# Motor2.net
KiCad netlist of a schematic drawn in Altium Designer
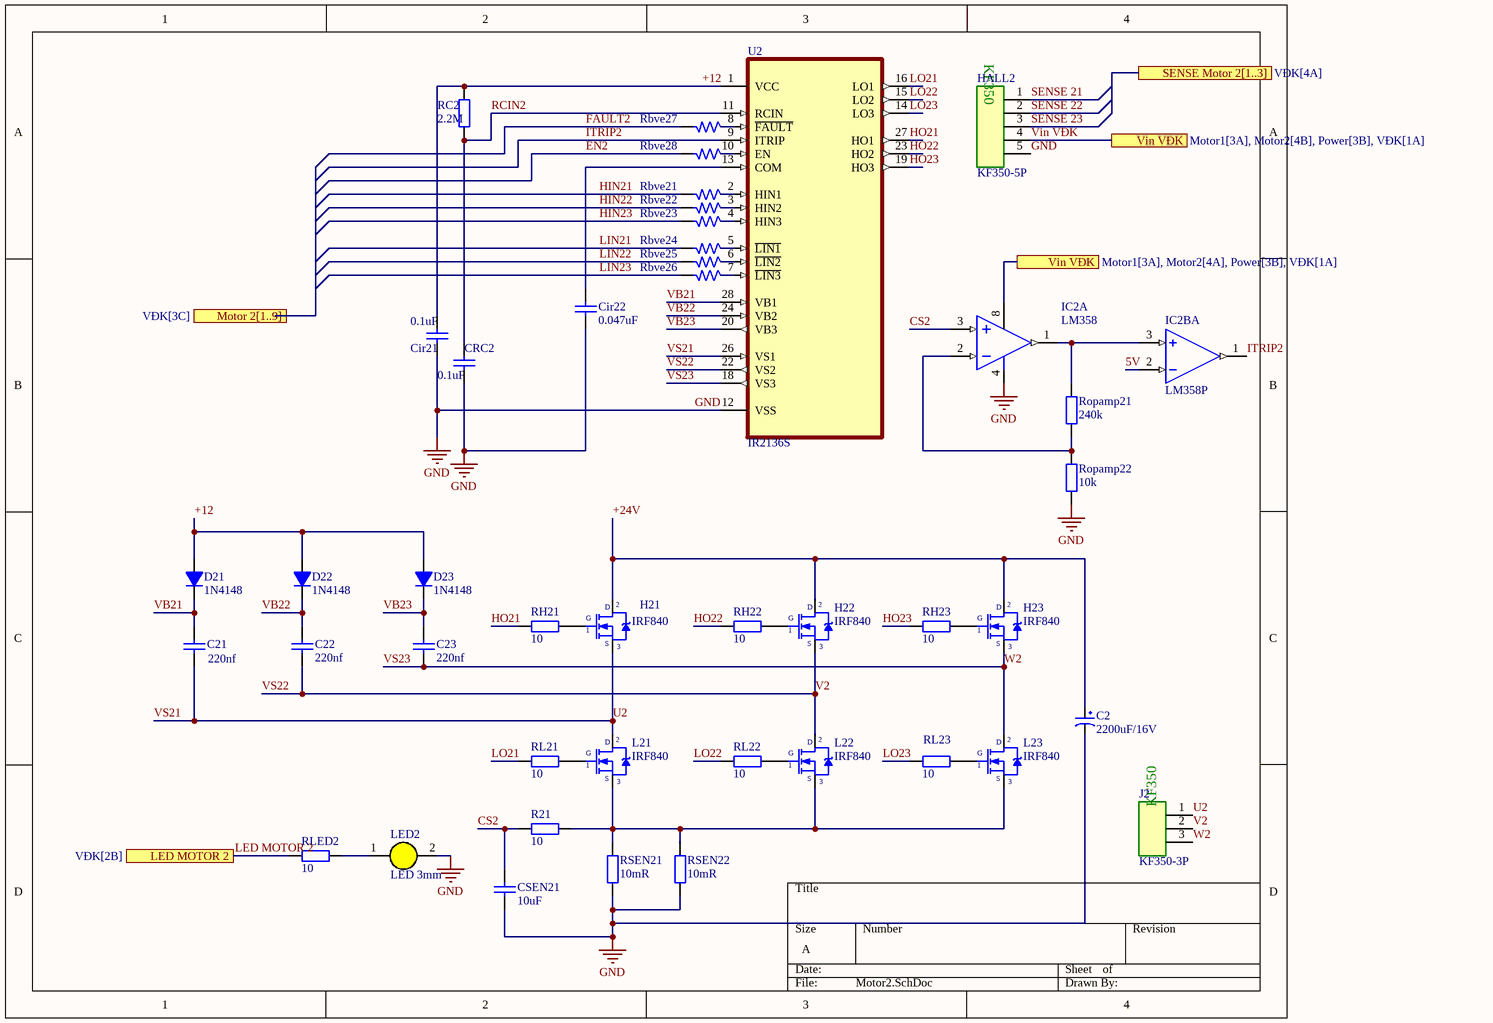
[diagram p0: Motor2.SchDoc]

(export (version "E")
  (design (tool "Eeschema 10.0.6"))
  (components
    (comp (ref "C2")
      (value "2200uF/16V")
      (footprint "CP2/4")
      (description "Cap 2200uF/16V - 1000uF/50V")
      (libsource (lib "SCH_Lib_Devzone") (part "CP5"))
    )
    (comp (ref "C21")
      (value "220nf")
      (footprint "Tu-pico")
      (description "Capacitor")
      (fields (field (name "Comment") "Capacitor Ceramic") (field (name "PUBLISHER") "Altium Limited"))
      (libsource (lib "Devzone_SCHLib") (part "CapCeramic"))
    )
    (comp (ref "C22")
      (value "220nf")
      (footprint "Tu-pico")
      (description "Capacitor")
      (fields (field (name "Comment") "Capacitor Ceramic") (field (name "PUBLISHER") "Altium Limited"))
      (libsource (lib "Devzone_SCHLib") (part "CapCeramic"))
    )
    (comp (ref "C23")
      (value "220nf")
      (footprint "Tu-pico")
      (description "Capacitor")
      (fields (field (name "Comment") "Capacitor Ceramic") (field (name "PUBLISHER") "Altium Limited"))
      (libsource (lib "Devzone_SCHLib") (part "CapCeramic"))
    )
    (comp (ref "Cir21")
      (value "0.1uF")
      (footprint "Tu-pico")
      (description "Capacitor")
      (fields (field (name "Comment") "Capacitor Ceramic") (field (name "PUBLISHER") "Altium Limited"))
      (libsource (lib "Devzone_SCHLib") (part "CapCeramic"))
    )
    (comp (ref "Cir22")
      (value "0.047uF")
      (footprint "Tu-pico")
      (description "Capacitor")
      (fields (field (name "Comment") "Capacitor Ceramic") (field (name "PUBLISHER") "Altium Limited"))
      (libsource (lib "Devzone_SCHLib") (part "CapCeramic"))
    )
    (comp (ref "CRC2")
      (value "0.1uF")
      (footprint "Tu-pico")
      (description "Capacitor")
      (fields (field (name "Comment") "Capacitor Ceramic") (field (name "PUBLISHER") "Altium Limited"))
      (libsource (lib "Devzone_SCHLib") (part "CapCeramic"))
    )
    (comp (ref "CSEN21")
      (value "10uF")
      (footprint "Tu-pico")
      (description "Capacitor")
      (fields (field (name "Comment") "Capacitor Ceramic") (field (name "PUBLISHER") "Altium Limited"))
      (libsource (lib "Devzone_SCHLib") (part "CapCeramic"))
    )
    (comp (ref "D21")
      (value "1N4148")
      (footprint "D0.5A")
      (description "D0.5A")
      (libsource (lib "Devzone_SCHLib") (part "D0.5A"))
    )
    (comp (ref "D22")
      (value "1N4148")
      (footprint "D0.5A")
      (description "D0.5A")
      (libsource (lib "Devzone_SCHLib") (part "D0.5A"))
    )
    (comp (ref "D23")
      (value "1N4148")
      (footprint "D0.5A")
      (description "D0.5A")
      (libsource (lib "Devzone_SCHLib") (part "D0.5A"))
    )
    (comp (ref "H21")
      (value "IRF840")
      (footprint "QTO-220")
      (description "MOSFET N - CHANNEL 500V - 0.75 - 8A - TO-220")
      (libsource (lib "Devzone_SCHLib") (part "IRF840"))
    )
    (comp (ref "H22")
      (value "IRF840")
      (footprint "QTO-220")
      (description "MOSFET N - CHANNEL 500V - 0.75 - 8A - TO-220")
      (libsource (lib "Devzone_SCHLib") (part "IRF840"))
    )
    (comp (ref "H23")
      (value "IRF840")
      (footprint "QTO-220")
      (description "MOSFET N - CHANNEL 500V - 0.75 - 8A - TO-220")
      (libsource (lib "Devzone_SCHLib") (part "IRF840"))
    )
    (comp (ref "HALL2") (value "KF350-5P") (footprint "KF350-5P") (libsource (lib "KF350") (part "KF350-5P")))
    (comp (ref "IC2")
      (value "LM358")
      (footprint "DIP8/W0.3")
      (description "Low-Power Dual Operational Amplifier")
      (libsource (lib "SCH_Lib_Devzone") (part "LM358"))
    )
    (comp (ref "IC2B")
      (value "LM358P")
      (footprint "DIP794W45P254L959H508Q8")
      (description "Dual, 30-V, 700-kHz operational amplifier")
      (fields (field (name "MF") "Texas Instruments"))
      (libsource (lib "LM358P") (part "LM358P"))
    )
    (comp (ref "J2") (value "KF350-3P") (footprint "KF350-3P") (libsource (lib "KF350") (part "KF350-3P")))
    (comp (ref "L21")
      (value "IRF840")
      (footprint "QTO-220")
      (description "MOSFET N - CHANNEL 500V - 0.75 - 8A - TO-220")
      (libsource (lib "Devzone_SCHLib") (part "IRF840"))
    )
    (comp (ref "L22")
      (value "IRF840")
      (footprint "QTO-220")
      (description "MOSFET N - CHANNEL 500V - 0.75 - 8A - TO-220")
      (libsource (lib "Devzone_SCHLib") (part "IRF840"))
    )
    (comp (ref "L23")
      (value "IRF840")
      (footprint "QTO-220")
      (description "MOSFET N - CHANNEL 500V - 0.75 - 8A - TO-220")
      (libsource (lib "Devzone_SCHLib") (part "IRF840"))
    )
    (comp (ref "LED2")
      (value "LED 3mm")
      (footprint "LED-3MM-YELLOW")
      (description "Cắm")
      (libsource (lib "Altium_Lib_by_KhueNguyenCreator") (part "LED 3mm Vang"))
    )
    (comp (ref "R21")
      (value "10")
      (footprint "R1/4W")
      (description "Resistor 1/4W")
      (libsource (lib "Devzone_SCHLib") (part "R1/4W"))
    )
    (comp (ref "Rbve21")
      (value "1m")
      (footprint "SM-1206")
      (description "Resistor 1/4W")
      (libsource (lib "SCH_Lib_Devzone") (part "R"))
    )
    (comp (ref "Rbve22")
      (value "1m")
      (footprint "SM-1206")
      (description "Resistor 1/4W")
      (libsource (lib "SCH_Lib_Devzone") (part "R"))
    )
    (comp (ref "Rbve23")
      (value "1m")
      (footprint "SM-1206")
      (description "Resistor 1/4W")
      (libsource (lib "SCH_Lib_Devzone") (part "R"))
    )
    (comp (ref "Rbve24")
      (value "1m")
      (footprint "SM-1206")
      (description "Resistor 1/4W")
      (libsource (lib "SCH_Lib_Devzone") (part "R"))
    )
    (comp (ref "Rbve25")
      (value "1m")
      (footprint "SM-1206")
      (description "Resistor 1/4W")
      (libsource (lib "SCH_Lib_Devzone") (part "R"))
    )
    (comp (ref "Rbve26")
      (value "1m")
      (footprint "SM-1206")
      (description "Resistor 1/4W")
      (libsource (lib "SCH_Lib_Devzone") (part "R"))
    )
    (comp (ref "Rbve27")
      (value "1m")
      (footprint "SM-1206")
      (description "Resistor 1/4W")
      (libsource (lib "SCH_Lib_Devzone") (part "R"))
    )
    (comp (ref "Rbve28")
      (value "1m")
      (footprint "SM-1206")
      (description "Resistor 1/4W")
      (libsource (lib "SCH_Lib_Devzone") (part "R"))
    )
    (comp (ref "RC2")
      (value "2.2M")
      (footprint "R1/4W")
      (description "Resistor 1/4W")
      (libsource (lib "Devzone_SCHLib") (part "R1/4W"))
    )
    (comp (ref "RH21")
      (value "10")
      (footprint "R1/4W")
      (description "Resistor 1/4W")
      (libsource (lib "Devzone_SCHLib") (part "R1/4W"))
    )
    (comp (ref "RH22")
      (value "10")
      (footprint "R1/4W")
      (description "Resistor 1/4W")
      (libsource (lib "Devzone_SCHLib") (part "R1/4W"))
    )
    (comp (ref "RH23")
      (value "10")
      (footprint "R1/4W")
      (description "Resistor 1/4W")
      (libsource (lib "Devzone_SCHLib") (part "R1/4W"))
    )
    (comp (ref "RL21")
      (value "10")
      (footprint "R1/4W")
      (description "Resistor 1/4W")
      (libsource (lib "Devzone_SCHLib") (part "R1/4W"))
    )
    (comp (ref "RL22")
      (value "10")
      (footprint "R1/4W")
      (description "Resistor 1/4W")
      (libsource (lib "Devzone_SCHLib") (part "R1/4W"))
    )
    (comp (ref "RL23")
      (value "10")
      (footprint "R1/4W")
      (description "Resistor 1/4W")
      (libsource (lib "Devzone_SCHLib") (part "R1/4W"))
    )
    (comp (ref "RLED2")
      (value "10")
      (footprint "R1/4W")
      (description "Resistor 1/4W")
      (libsource (lib "Devzone_SCHLib") (part "R1/4W"))
    )
    (comp (ref "Ropamp21")
      (value "240k")
      (footprint "R1/4W")
      (description "Resistor 1/4W")
      (libsource (lib "Devzone_SCHLib") (part "R1/4W"))
    )
    (comp (ref "Ropamp22")
      (value "10k")
      (footprint "R1/4W")
      (description "Resistor 1/4W")
      (libsource (lib "Devzone_SCHLib") (part "R1/4W"))
    )
    (comp (ref "RSEN21")
      (value "10mR")
      (footprint "Shunt 10mR 1.2x10x7MM")
      (description "Shunt 10mR 1.2x10x7MM")
      (libsource (lib "SCH_Lib_Devzone") (part "Shunt 10mR 1.2x10x7MM"))
    )
    (comp (ref "RSEN22")
      (value "10mR")
      (footprint "Shunt 10mR 1.2x10x7MM")
      (description "Shunt 10mR 1.2x10x7MM")
      (libsource (lib "SCH_Lib_Devzone") (part "Shunt 10mR 1.2x10x7MM"))
    )
    (comp (ref "U2")
      (value "IR2136S")
      (footprint "SOIC127PX1032X265-28N")
      (description "IC Ä‘iá»u khiá»ƒn ná»­a cáº§u cá»•ng Ä‘áº£o ngÆ°á»£c 28-SOIC")
      (fields (field (name "MF") "Infineon"))
      (libsource (lib "IR2136S") (part "IR2136S"))
    )
  )
  (nets
    (net (code "1") (name "/+12") (class "Default")
      (node (ref "Cir21") (pin "1") (pinfunction "1_1") (pintype "passive"))
      (node (ref "D21") (pin "1") (pinfunction "A_1") (pintype "passive"))
      (node (ref "D22") (pin "1") (pinfunction "A_1") (pintype "passive"))
      (node (ref "D23") (pin "1") (pinfunction "A_1") (pintype "passive"))
      (node (ref "RC2") (pin "2") (pinfunction "2_2") (pintype "passive"))
      (node (ref "U2") (pin "1") (pinfunction "VCC_1") (pintype "power_in"))
    )
    (net (code "2") (name "/+24V") (class "Default")
      (node (ref "C2") (pin "1") (pinfunction "1_1") (pintype "passive"))
      (node (ref "H21") (pin "2") (pinfunction "D_2") (pintype "passive"))
      (node (ref "H22") (pin "2") (pinfunction "D_2") (pintype "passive"))
      (node (ref "H23") (pin "2") (pinfunction "D_2") (pintype "passive"))
    )
    (net (code "3") (name "/5V") (class "Default")
      (node (ref "IC2B") (pin "2") (pinfunction "-IN1_2") (pintype "input"))
    )
    (net (code "4") (name "/CS2") (class "Default")
      (node (ref "CSEN21") (pin "1") (pinfunction "1_1") (pintype "passive"))
      (node (ref "IC2") (pin "3") (pinfunction "IN+_3") (pintype "input"))
      (node (ref "R21") (pin "2") (pinfunction "2_2") (pintype "passive"))
    )
    (net (code "5") (name "/EN2") (class "Default")
      (node (ref "Rbve28") (pin "2") (pinfunction "2_2") (pintype "passive"))
    )
    (net (code "6") (name "/FAULT2") (class "Default")
      (node (ref "Rbve27") (pin "2") (pinfunction "2_2") (pintype "passive"))
    )
    (net (code "7") (name "/HIN21") (class "Default")
      (node (ref "Rbve21") (pin "2") (pinfunction "2_2") (pintype "passive"))
    )
    (net (code "8") (name "/HIN22") (class "Default")
      (node (ref "Rbve22") (pin "2") (pinfunction "2_2") (pintype "passive"))
    )
    (net (code "9") (name "/HIN23") (class "Default")
      (node (ref "Rbve23") (pin "2") (pinfunction "2_2") (pintype "passive"))
    )
    (net (code "10") (name "/HO21") (class "Default")
      (node (ref "RH21") (pin "1") (pinfunction "1_1") (pintype "passive"))
      (node (ref "U2") (pin "27") (pinfunction "HO1_27") (pintype "output"))
    )
    (net (code "11") (name "/HO22") (class "Default")
      (node (ref "RH22") (pin "1") (pinfunction "1_1") (pintype "passive"))
      (node (ref "U2") (pin "23") (pinfunction "HO2_23") (pintype "output"))
    )
    (net (code "12") (name "/HO23") (class "Default")
      (node (ref "RH23") (pin "1") (pinfunction "1_1") (pintype "passive"))
      (node (ref "U2") (pin "19") (pinfunction "HO3_19") (pintype "output"))
    )
    (net (code "13") (name "/ITRIP2") (class "Default")
      (node (ref "IC2B") (pin "1") (pinfunction "OUT1_1") (pintype "output"))
      (node (ref "U2") (pin "9") (pinfunction "ITRIP_9") (pintype "input"))
    )
    (net (code "14") (name "/LED MOTOR 2") (class "Default")
      (node (ref "RLED2") (pin "2") (pinfunction "2_2") (pintype "passive"))
    )
    (net (code "15") (name "/LIN21") (class "Default")
      (node (ref "Rbve24") (pin "2") (pinfunction "2_2") (pintype "passive"))
    )
    (net (code "16") (name "/LIN22") (class "Default")
      (node (ref "Rbve25") (pin "2") (pinfunction "2_2") (pintype "passive"))
    )
    (net (code "17") (name "/LIN23") (class "Default")
      (node (ref "Rbve26") (pin "2") (pinfunction "2_2") (pintype "passive"))
    )
    (net (code "18") (name "/LO21") (class "Default")
      (node (ref "RL21") (pin "1") (pinfunction "1_1") (pintype "passive"))
      (node (ref "U2") (pin "16") (pinfunction "LO1_16") (pintype "output"))
    )
    (net (code "19") (name "/LO22") (class "Default")
      (node (ref "RL22") (pin "1") (pinfunction "1_1") (pintype "passive"))
      (node (ref "U2") (pin "15") (pinfunction "LO2_15") (pintype "output"))
    )
    (net (code "20") (name "/LO23") (class "Default")
      (node (ref "RL23") (pin "2") (pinfunction "2_2") (pintype "passive"))
      (node (ref "U2") (pin "14") (pinfunction "LO3_14") (pintype "output"))
    )
    (net (code "22") (name "/RCIN2") (class "Default")
      (node (ref "CRC2") (pin "1") (pinfunction "1_1") (pintype "passive"))
      (node (ref "RC2") (pin "1") (pinfunction "1_1") (pintype "passive"))
      (node (ref "U2") (pin "11") (pinfunction "RCIN_11") (pintype "input"))
    )
    (net (code "23") (name "/SENSE 21") (class "Default")
      (node (ref "HALL2") (pin "1") (pinfunction "1_1") (pintype "passive"))
    )
    (net (code "24") (name "/SENSE 22") (class "Default")
      (node (ref "HALL2") (pin "2") (pinfunction "2_2") (pintype "passive"))
    )
    (net (code "25") (name "/SENSE 23") (class "Default")
      (node (ref "HALL2") (pin "3") (pinfunction "3_3") (pintype "passive"))
    )
    (net (code "27") (name "/U2") (class "Default")
      (node (ref "C21") (pin "2") (pinfunction "2_2") (pintype "passive"))
      (node (ref "H21") (pin "3") (pinfunction "S_3") (pintype "passive"))
      (node (ref "J2") (pin "1") (pinfunction "1_1") (pintype "passive"))
      (node (ref "L21") (pin "2") (pinfunction "D_2") (pintype "passive"))
      (node (ref "U2") (pin "26") (pinfunction "VS1_26") (pintype "input"))
    )
    (net (code "28") (name "/V2") (class "Default")
      (node (ref "C22") (pin "2") (pinfunction "2_2") (pintype "passive"))
      (node (ref "H22") (pin "3") (pinfunction "S_3") (pintype "passive"))
      (node (ref "J2") (pin "2") (pinfunction "2_2") (pintype "passive"))
      (node (ref "L22") (pin "2") (pinfunction "D_2") (pintype "passive"))
      (node (ref "U2") (pin "22") (pinfunction "VS2_22") (pintype "output"))
    )
    (net (code "29") (name "/VB21") (class "Default")
      (node (ref "C21") (pin "1") (pinfunction "1_1") (pintype "passive"))
      (node (ref "D21") (pin "2") (pinfunction "K_2") (pintype "passive"))
      (node (ref "U2") (pin "28") (pinfunction "VB1_28") (pintype "input"))
    )
    (net (code "30") (name "/VB22") (class "Default")
      (node (ref "C22") (pin "1") (pinfunction "1_1") (pintype "passive"))
      (node (ref "D22") (pin "2") (pinfunction "K_2") (pintype "passive"))
      (node (ref "U2") (pin "24") (pinfunction "VB2_24") (pintype "input"))
    )
    (net (code "31") (name "/VB23") (class "Default")
      (node (ref "C23") (pin "1") (pinfunction "1_1") (pintype "passive"))
      (node (ref "D23") (pin "2") (pinfunction "K_2") (pintype "passive"))
      (node (ref "U2") (pin "20") (pinfunction "VB3_20") (pintype "output"))
    )
    (net (code "32") (name "/VS23") (class "Default")
      (node (ref "C23") (pin "2") (pinfunction "2_2") (pintype "passive"))
      (node (ref "H23") (pin "3") (pinfunction "S_3") (pintype "passive"))
      (node (ref "J2") (pin "3") (pinfunction "3_3") (pintype "passive"))
      (node (ref "L23") (pin "2") (pinfunction "D_2") (pintype "passive"))
      (node (ref "U2") (pin "18") (pinfunction "VS3_18") (pintype "output"))
    )
    (net (code "33") (name "/Vin VĐK") (class "Default")
      (node (ref "HALL2") (pin "4") (pinfunction "4_4") (pintype "passive"))
      (node (ref "IC2") (pin "8") (pinfunction "+V_8") (pintype "passive"))
    )
    (net (code "34") (name "GND") (class "Default")
      (node (ref "C2") (pin "2") (pinfunction "2_2") (pintype "passive"))
      (node (ref "CRC2") (pin "2") (pinfunction "2_2") (pintype "passive"))
      (node (ref "CSEN21") (pin "2") (pinfunction "2_2") (pintype "passive"))
      (node (ref "Cir21") (pin "2") (pinfunction "2_2") (pintype "passive"))
      (node (ref "Cir22") (pin "2") (pinfunction "2_2") (pintype "passive"))
      (node (ref "HALL2") (pin "5") (pinfunction "5_5") (pintype "passive"))
      (node (ref "IC2") (pin "4") (pinfunction "-V_4") (pintype "passive"))
      (node (ref "LED2") (pin "2") (pinfunction "K_2") (pintype "passive"))
      (node (ref "RSEN21") (pin "1") (pinfunction "1_1") (pintype "passive"))
      (node (ref "RSEN22") (pin "1") (pinfunction "1_1") (pintype "passive"))
      (node (ref "Ropamp22") (pin "2") (pinfunction "2_2") (pintype "passive"))
      (node (ref "U2") (pin "12") (pinfunction "VSS_12") (pintype "passive"))
    )
    (net (code "35") (name "Net-(H21-G)") (class "Default")
      (node (ref "H21") (pin "1") (pinfunction "G_1") (pintype "passive"))
      (node (ref "RH21") (pin "2") (pinfunction "2_2") (pintype "passive"))
    )
    (net (code "36") (name "Net-(H22-G)") (class "Default")
      (node (ref "H22") (pin "1") (pinfunction "G_1") (pintype "passive"))
      (node (ref "RH22") (pin "2") (pinfunction "2_2") (pintype "passive"))
    )
    (net (code "37") (name "Net-(H23-G)") (class "Default")
      (node (ref "H23") (pin "1") (pinfunction "G_1") (pintype "passive"))
      (node (ref "RH23") (pin "2") (pinfunction "2_2") (pintype "passive"))
    )
    (net (code "38") (name "Net-(IC2A-IN-)") (class "Default")
      (node (ref "IC2") (pin "2") (pinfunction "IN-_2") (pintype "input"))
      (node (ref "Ropamp21") (pin "2") (pinfunction "2_2") (pintype "passive"))
      (node (ref "Ropamp22") (pin "1") (pinfunction "1_1") (pintype "passive"))
    )
    (net (code "39") (name "Net-(IC2A-OUT)") (class "Default")
      (node (ref "IC2") (pin "1") (pinfunction "OUT_1") (pintype "output"))
      (node (ref "IC2B") (pin "3") (pinfunction "+IN1_3") (pintype "input"))
      (node (ref "Ropamp21") (pin "1") (pinfunction "1_1") (pintype "passive"))
    )
    (net (code "40") (name "Net-(L21-G)") (class "Default")
      (node (ref "L21") (pin "1") (pinfunction "G_1") (pintype "passive"))
      (node (ref "RL21") (pin "2") (pinfunction "2_2") (pintype "passive"))
    )
    (net (code "41") (name "Net-(L21-S)") (class "Default")
      (node (ref "L21") (pin "3") (pinfunction "S_3") (pintype "passive"))
      (node (ref "L22") (pin "3") (pinfunction "S_3") (pintype "passive"))
      (node (ref "L23") (pin "3") (pinfunction "S_3") (pintype "passive"))
      (node (ref "R21") (pin "1") (pinfunction "1_1") (pintype "passive"))
      (node (ref "RSEN21") (pin "2") (pinfunction "2_2") (pintype "passive"))
      (node (ref "RSEN22") (pin "2") (pinfunction "2_2") (pintype "passive"))
    )
    (net (code "42") (name "Net-(L22-G)") (class "Default")
      (node (ref "L22") (pin "1") (pinfunction "G_1") (pintype "passive"))
      (node (ref "RL22") (pin "2") (pinfunction "2_2") (pintype "passive"))
    )
    (net (code "43") (name "Net-(L23-G)") (class "Default")
      (node (ref "L23") (pin "1") (pinfunction "G_1") (pintype "passive"))
      (node (ref "RL23") (pin "1") (pinfunction "1_1") (pintype "passive"))
    )
    (net (code "44") (name "Net-(LED2-A)") (class "Default")
      (node (ref "LED2") (pin "1") (pinfunction "A_1") (pintype "passive"))
      (node (ref "RLED2") (pin "1") (pinfunction "1_1") (pintype "passive"))
    )
    (net (code "45") (name "Net-(U2-COM)") (class "Default")
      (node (ref "Cir22") (pin "1") (pinfunction "1_1") (pintype "passive"))
      (node (ref "U2") (pin "13") (pinfunction "COM_13") (pintype "input"))
    )
    (net (code "46") (name "Net-(U2-EN)") (class "Default")
      (node (ref "Rbve28") (pin "1") (pinfunction "1_1") (pintype "passive"))
      (node (ref "U2") (pin "10") (pinfunction "EN_10") (pintype "input"))
    )
    (net (code "47") (name "Net-(U2-HIN1)") (class "Default")
      (node (ref "Rbve21") (pin "1") (pinfunction "1_1") (pintype "passive"))
      (node (ref "U2") (pin "2") (pinfunction "HIN1_2") (pintype "input"))
    )
    (net (code "48") (name "Net-(U2-HIN2)") (class "Default")
      (node (ref "Rbve22") (pin "1") (pinfunction "1_1") (pintype "passive"))
      (node (ref "U2") (pin "3") (pinfunction "HIN2_3") (pintype "input"))
    )
    (net (code "49") (name "Net-(U2-HIN3)") (class "Default")
      (node (ref "Rbve23") (pin "1") (pinfunction "1_1") (pintype "passive"))
      (node (ref "U2") (pin "4") (pinfunction "HIN3_4") (pintype "input"))
    )
    (net (code "50") (name "Net-(U2-~{FAULT})") (class "Default")
      (node (ref "Rbve27") (pin "1") (pinfunction "1_1") (pintype "passive"))
      (node (ref "U2") (pin "8") (pinfunction "~{FAULT}_8") (pintype "input"))
    )
    (net (code "51") (name "Net-(U2-~{LIN1})") (class "Default")
      (node (ref "Rbve24") (pin "1") (pinfunction "1_1") (pintype "passive"))
      (node (ref "U2") (pin "5") (pinfunction "~{LIN1}_5") (pintype "input"))
    )
    (net (code "52") (name "Net-(U2-~{LIN2})") (class "Default")
      (node (ref "Rbve25") (pin "1") (pinfunction "1_1") (pintype "passive"))
      (node (ref "U2") (pin "6") (pinfunction "~{LIN2}_6") (pintype "input"))
    )
    (net (code "53") (name "Net-(U2-~{LIN3})") (class "Default")
      (node (ref "Rbve26") (pin "1") (pinfunction "1_1") (pintype "passive"))
      (node (ref "U2") (pin "7") (pinfunction "~{LIN3}_7") (pintype "input"))
    )
  )
)
